# SCH.net
KiCad netlist of a schematic drawn in Altium Designer
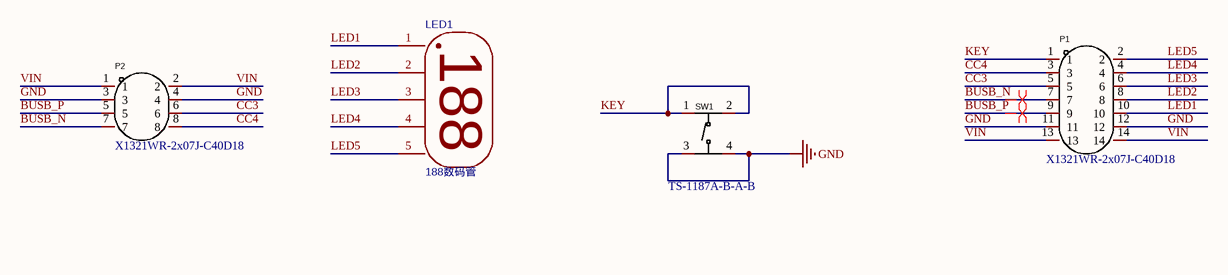
[diagram p0: SCH.SchDoc]

(export (version "E")
  (design (tool "Eeschema 10.0.6"))
  (components
    (comp (ref "LED1")
      (value "188数码管")
      (footprint "LED_188")
      (fields (field (name "CONTRIBUTOR") "微雪智能"))
      (libsource (lib "DHO800_Battery_Pack_IP5389_V1.0_2") (part "188数码管"))
    )
    (comp (ref "P1")
      (value "X1321WR-2x07J-C40D18")
      (footprint "HDR-TH_14P-P1.27-H-M-R2-C7-S1.27-W7.5-N")
      (fields (field (name "MANUFACTURER") "XKB Connectivity(中国星坤)"))
      (libsource (lib "altium-import") (part "root_0_X1321WR-2x07J-C40D18_"))
    )
    (comp (ref "P2")
      (value "X1321WR-2x07J-C40D18")
      (footprint "HDR-TH_8P-P1.27")
      (description "双排弯针2*4P")
      (fields (field (name "MANUFACTURER") "XKB Connectivity(中国星坤)"))
      (libsource (lib "DHO800_Battery_Pack_LED_V1.0") (part "双排插针"))
    )
    (comp (ref "SW1")
      (value "TS-1187A-B-A-B")
      (footprint "SW-SMD_4P-L5.1-W5.1-P3.70-LS6.5-TL-2")
      (description "按键")
      (fields (field (name "MANUFACTURER") "XKB Connectivity(中国星坤)"))
      (libsource (lib "DHO800_Battery_Pack_IP5389_V1.0_2") (part "TS-1187A-B-A-B"))
    )
  )
  (nets
    (net (code "1") (name "/BUSB_N") (class "Default")
      (node (ref "P1") (pin "7") (pinfunction "7_7") (pintype "passive"))
      (node (ref "P2") (pin "7") (pinfunction "7_7") (pintype "passive"))
    )
    (net (code "2") (name "/BUSB_P") (class "Default")
      (node (ref "P1") (pin "9") (pinfunction "9_9") (pintype "passive"))
      (node (ref "P2") (pin "5") (pinfunction "5_5") (pintype "passive"))
    )
    (net (code "3") (name "/CC3") (class "Default")
      (node (ref "P1") (pin "5") (pinfunction "5_5") (pintype "passive"))
      (node (ref "P2") (pin "6") (pinfunction "6_6") (pintype "passive"))
    )
    (net (code "4") (name "/CC4") (class "Default")
      (node (ref "P1") (pin "3") (pinfunction "3_3") (pintype "passive"))
      (node (ref "P2") (pin "8") (pinfunction "8_8") (pintype "passive"))
    )
    (net (code "5") (name "/KEY") (class "Default")
      (node (ref "P1") (pin "1") (pinfunction "1_1") (pintype "passive"))
      (node (ref "SW1") (pin "1") (pinfunction "A_1") (pintype "passive"))
      (node (ref "SW1") (pin "2") (pinfunction "B_2") (pintype "passive"))
    )
    (net (code "6") (name "/LED1") (class "Default")
      (node (ref "LED1") (pin "1") (pinfunction "1_1") (pintype "passive"))
      (node (ref "P1") (pin "10") (pinfunction "10_10") (pintype "passive"))
    )
    (net (code "7") (name "/LED2") (class "Default")
      (node (ref "LED1") (pin "2") (pinfunction "2_2") (pintype "passive"))
      (node (ref "P1") (pin "8") (pinfunction "8_8") (pintype "passive"))
    )
    (net (code "8") (name "/LED3") (class "Default")
      (node (ref "LED1") (pin "3") (pinfunction "3_3") (pintype "passive"))
      (node (ref "P1") (pin "6") (pinfunction "6_6") (pintype "passive"))
    )
    (net (code "9") (name "/LED4") (class "Default")
      (node (ref "LED1") (pin "4") (pinfunction "4_4") (pintype "passive"))
      (node (ref "P1") (pin "4") (pinfunction "4_4") (pintype "passive"))
    )
    (net (code "10") (name "/LED5") (class "Default")
      (node (ref "LED1") (pin "5") (pinfunction "5_5") (pintype "passive"))
      (node (ref "P1") (pin "2") (pinfunction "2_2") (pintype "passive"))
    )
    (net (code "11") (name "/VIN") (class "Default")
      (node (ref "P1") (pin "13") (pinfunction "13_13") (pintype "passive"))
      (node (ref "P1") (pin "14") (pinfunction "14_14") (pintype "passive"))
      (node (ref "P2") (pin "1") (pinfunction "1_1") (pintype "passive"))
      (node (ref "P2") (pin "2") (pinfunction "2_2") (pintype "passive"))
    )
    (net (code "12") (name "GND") (class "Default")
      (node (ref "P1") (pin "11") (pinfunction "11_11") (pintype "passive"))
      (node (ref "P1") (pin "12") (pinfunction "12_12") (pintype "passive"))
      (node (ref "P2") (pin "3") (pinfunction "3_3") (pintype "passive"))
      (node (ref "P2") (pin "4") (pinfunction "4_4") (pintype "passive"))
      (node (ref "SW1") (pin "3") (pinfunction "C_3") (pintype "passive"))
      (node (ref "SW1") (pin "4") (pinfunction "D_4") (pintype "passive"))
    )
  )
)
